# LED_Board_LED.net
KiCad netlist of a schematic drawn in Altium Designer
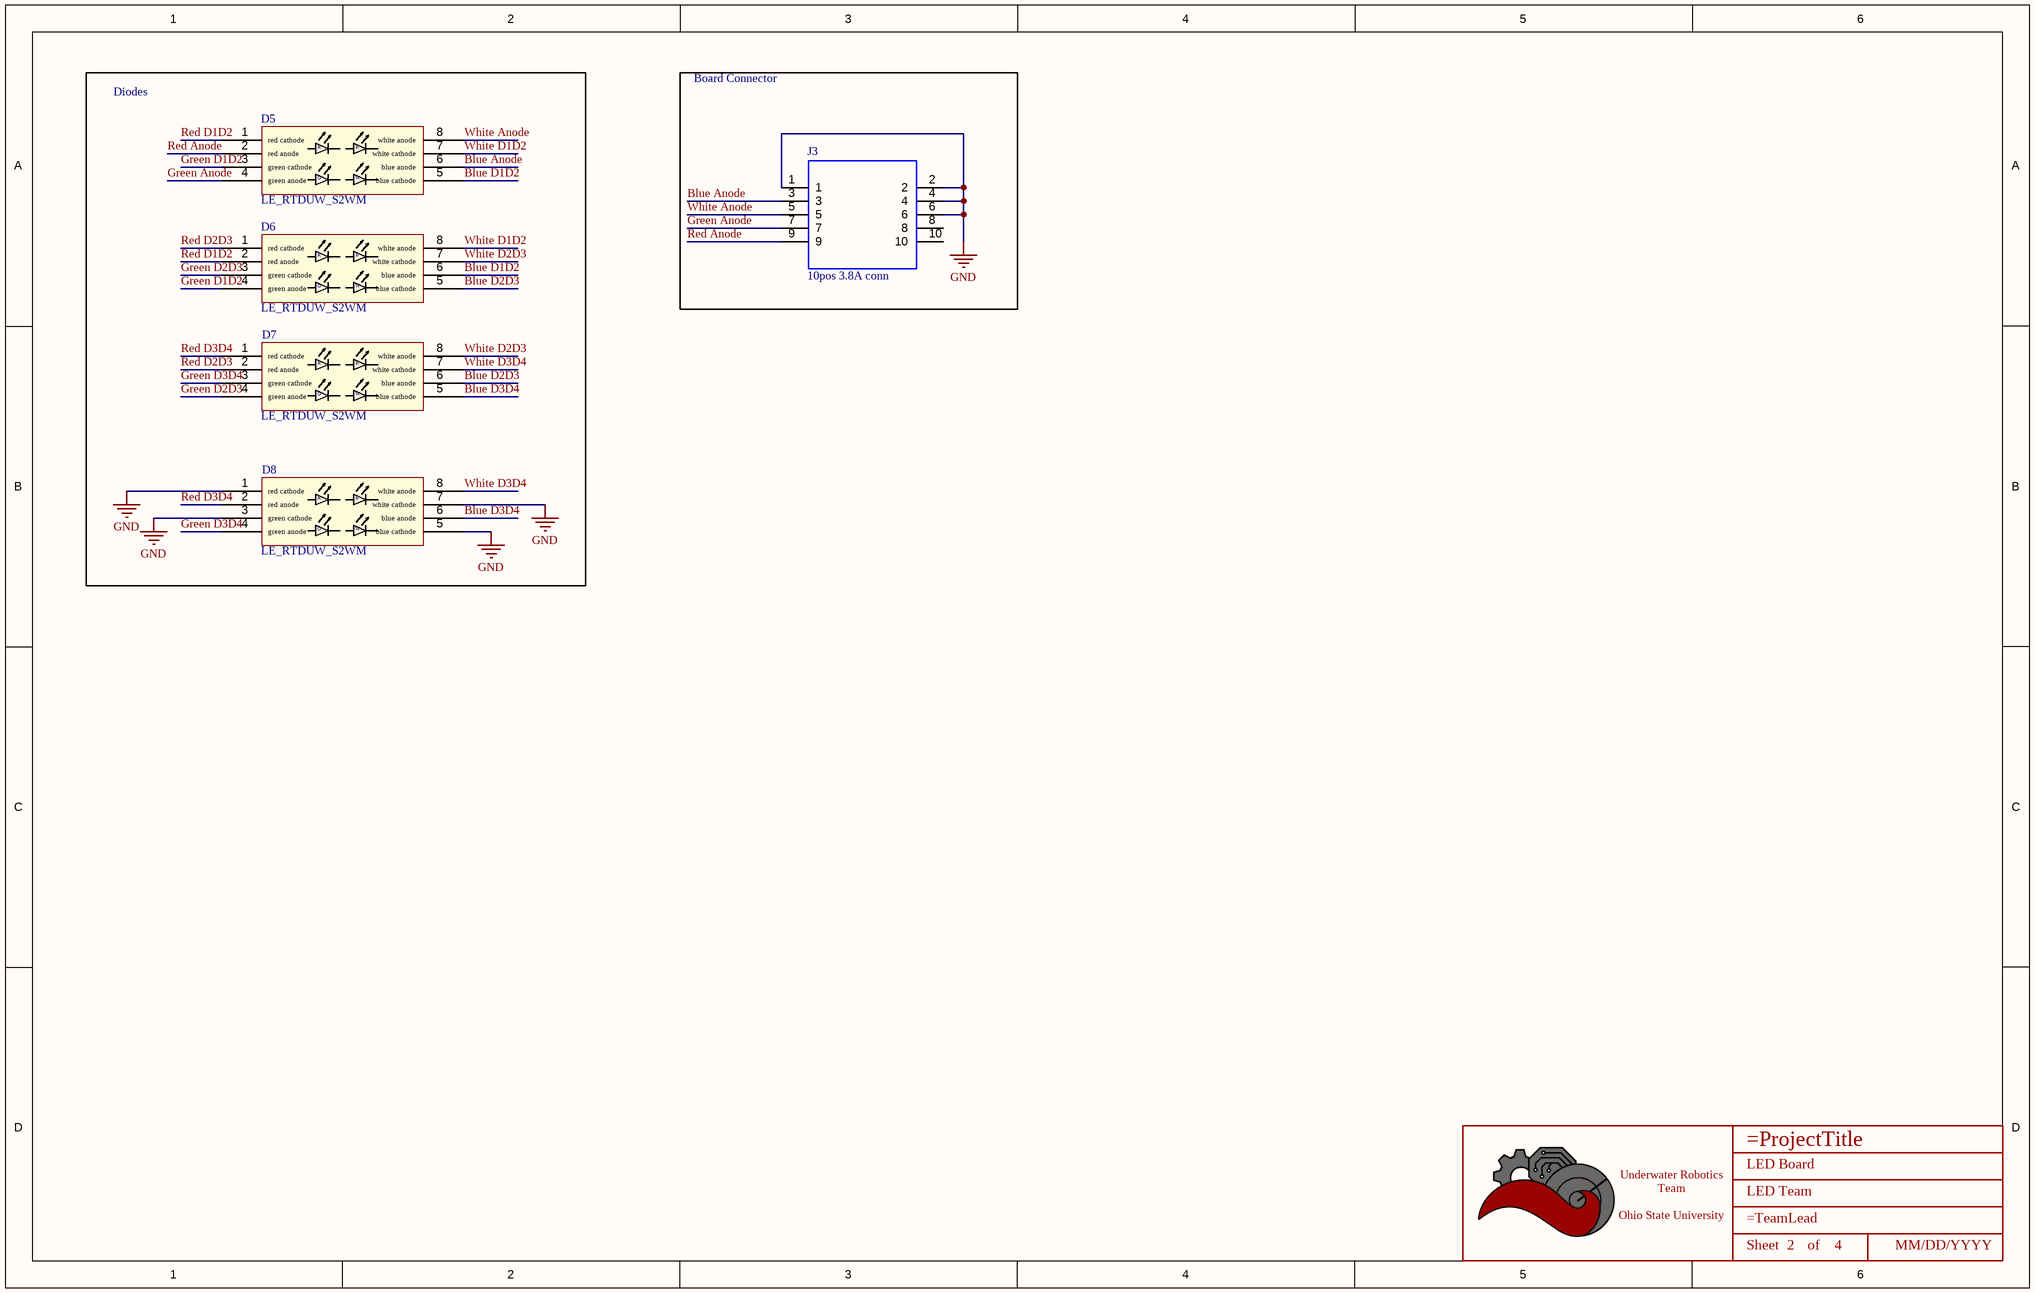
[diagram p0: LED_Board_LED.SchDoc]

(export (version "E")
  (design (tool "Eeschema 10.0.6"))
  (components
    (comp (ref "*")
      (value "Title_Block")
      (footprint "LOGO")
      (description "UWRT Schematic Title Block Template\r\n\r\nCreated June 2021, Dylan Trainor")
      (libsource (lib "UWRT") (part "Title_Block"))
    )
    (comp (ref "D5")
      (value "LE_RTDUW_S2WM")
      (description "LED OSTAR RGBW 625/527/453NM SMD")
      (libsource (lib "Diodes") (part "LE_RTDUW_S2WM"))
    )
    (comp (ref "D6")
      (value "LE_RTDUW_S2WM")
      (description "LED OSTAR RGBW 625/527/453NM SMD")
      (libsource (lib "Diodes") (part "LE_RTDUW_S2WM"))
    )
    (comp (ref "D7")
      (value "LE_RTDUW_S2WM")
      (description "LED OSTAR RGBW 625/527/453NM SMD")
      (libsource (lib "Diodes") (part "LE_RTDUW_S2WM"))
    )
    (comp (ref "D8")
      (value "LE_RTDUW_S2WM")
      (description "LED OSTAR RGBW 625/527/453NM SMD")
      (libsource (lib "Diodes") (part "LE_RTDUW_S2WM"))
    )
    (comp (ref "J3")
      (value "10pos 3.8A conn")
      (footprint "SAMTEC-LS2-105-01-X-D-RA2")
      (description "10 Position Connector Self Mating, Non-Gendered, Hermaphroditic Through Hole, Right Angle Gold")
      (fields (field (name "MP") "SAMTEC-LS2-105-01-X-D-RA2"))
      (libsource (lib "Connectors") (part "SAMTEC-LS2-105-01-X-D-RA2"))
    )
  )
  (nets
    (net (code "1") (name "/Blue Anode") (class "Default")
      (node (ref "D5") (pin "6") (pinfunction "blue_anode_6") (pintype "passive"))
      (node (ref "J3") (pin "3") (pinfunction "3_3") (pintype "passive"))
    )
    (net (code "2") (name "/Blue D1D2") (class "Default")
      (node (ref "D5") (pin "5") (pinfunction "blue_cathode_5") (pintype "passive"))
      (node (ref "D6") (pin "6") (pinfunction "blue_anode_6") (pintype "passive"))
    )
    (net (code "3") (name "/Blue D2D3") (class "Default")
      (node (ref "D6") (pin "5") (pinfunction "blue_cathode_5") (pintype "passive"))
      (node (ref "D7") (pin "6") (pinfunction "blue_anode_6") (pintype "passive"))
    )
    (net (code "4") (name "/Blue D3D4") (class "Default")
      (node (ref "D7") (pin "5") (pinfunction "blue_cathode_5") (pintype "passive"))
      (node (ref "D8") (pin "6") (pinfunction "blue_anode_6") (pintype "passive"))
    )
    (net (code "5") (name "/Green Anode") (class "Default")
      (node (ref "D5") (pin "4") (pinfunction "green_anode_4") (pintype "passive"))
      (node (ref "J3") (pin "7") (pinfunction "7_7") (pintype "passive"))
    )
    (net (code "6") (name "/Green D1D2") (class "Default")
      (node (ref "D5") (pin "3") (pinfunction "green_cathode_3") (pintype "passive"))
      (node (ref "D6") (pin "4") (pinfunction "green_anode_4") (pintype "passive"))
    )
    (net (code "7") (name "/Green D2D3") (class "Default")
      (node (ref "D6") (pin "3") (pinfunction "green_cathode_3") (pintype "passive"))
      (node (ref "D7") (pin "4") (pinfunction "green_anode_4") (pintype "passive"))
    )
    (net (code "8") (name "/Green D3D4") (class "Default")
      (node (ref "D7") (pin "3") (pinfunction "green_cathode_3") (pintype "passive"))
      (node (ref "D8") (pin "4") (pinfunction "green_anode_4") (pintype "passive"))
    )
    (net (code "9") (name "/Red Anode") (class "Default")
      (node (ref "D5") (pin "2") (pinfunction "red_anode_2") (pintype "passive"))
      (node (ref "J3") (pin "9") (pinfunction "9_9") (pintype "passive"))
    )
    (net (code "10") (name "/Red D1D2") (class "Default")
      (node (ref "D5") (pin "1") (pinfunction "red_cathode_1") (pintype "passive"))
      (node (ref "D6") (pin "2") (pinfunction "red_anode_2") (pintype "passive"))
    )
    (net (code "11") (name "/Red D2D3") (class "Default")
      (node (ref "D6") (pin "1") (pinfunction "red_cathode_1") (pintype "passive"))
      (node (ref "D7") (pin "2") (pinfunction "red_anode_2") (pintype "passive"))
    )
    (net (code "12") (name "/Red D3D4") (class "Default")
      (node (ref "D7") (pin "1") (pinfunction "red_cathode_1") (pintype "passive"))
      (node (ref "D8") (pin "2") (pinfunction "red_anode_2") (pintype "passive"))
    )
    (net (code "13") (name "/White Anode") (class "Default")
      (node (ref "D5") (pin "8") (pinfunction "white_anode_8") (pintype "passive"))
      (node (ref "J3") (pin "5") (pinfunction "5_5") (pintype "passive"))
    )
    (net (code "14") (name "/White D1D2") (class "Default")
      (node (ref "D5") (pin "7") (pinfunction "white_cathode_7") (pintype "passive"))
      (node (ref "D6") (pin "8") (pinfunction "white_anode_8") (pintype "passive"))
    )
    (net (code "15") (name "/White D2D3") (class "Default")
      (node (ref "D6") (pin "7") (pinfunction "white_cathode_7") (pintype "passive"))
      (node (ref "D7") (pin "8") (pinfunction "white_anode_8") (pintype "passive"))
    )
    (net (code "16") (name "/White D3D4") (class "Default")
      (node (ref "D7") (pin "7") (pinfunction "white_cathode_7") (pintype "passive"))
      (node (ref "D8") (pin "8") (pinfunction "white_anode_8") (pintype "passive"))
    )
    (net (code "17") (name "GND") (class "Default")
      (node (ref "D8") (pin "1") (pinfunction "red_cathode_1") (pintype "passive"))
      (node (ref "D8") (pin "3") (pinfunction "green_cathode_3") (pintype "passive"))
      (node (ref "D8") (pin "5") (pinfunction "blue_cathode_5") (pintype "passive"))
      (node (ref "D8") (pin "7") (pinfunction "white_cathode_7") (pintype "passive"))
      (node (ref "J3") (pin "1") (pinfunction "1_1") (pintype "passive"))
      (node (ref "J3") (pin "2") (pinfunction "2_2") (pintype "passive"))
      (node (ref "J3") (pin "4") (pinfunction "4_4") (pintype "passive"))
      (node (ref "J3") (pin "6") (pinfunction "6_6") (pintype "passive"))
    )
    (net (code "18") (name "unconnected-(J3-Pad8)") (class "Default")
      (node (ref "J3") (pin "8") (pinfunction "8_8") (pintype "passive"))
    )
    (net (code "19") (name "unconnected-(J3-Pad10)") (class "Default")
      (node (ref "J3") (pin "10") (pinfunction "10_10") (pintype "passive"))
    )
  )
)
